# INA333_ADS1118_yusnows.net
KiCad netlist of a schematic drawn in Altium Designer
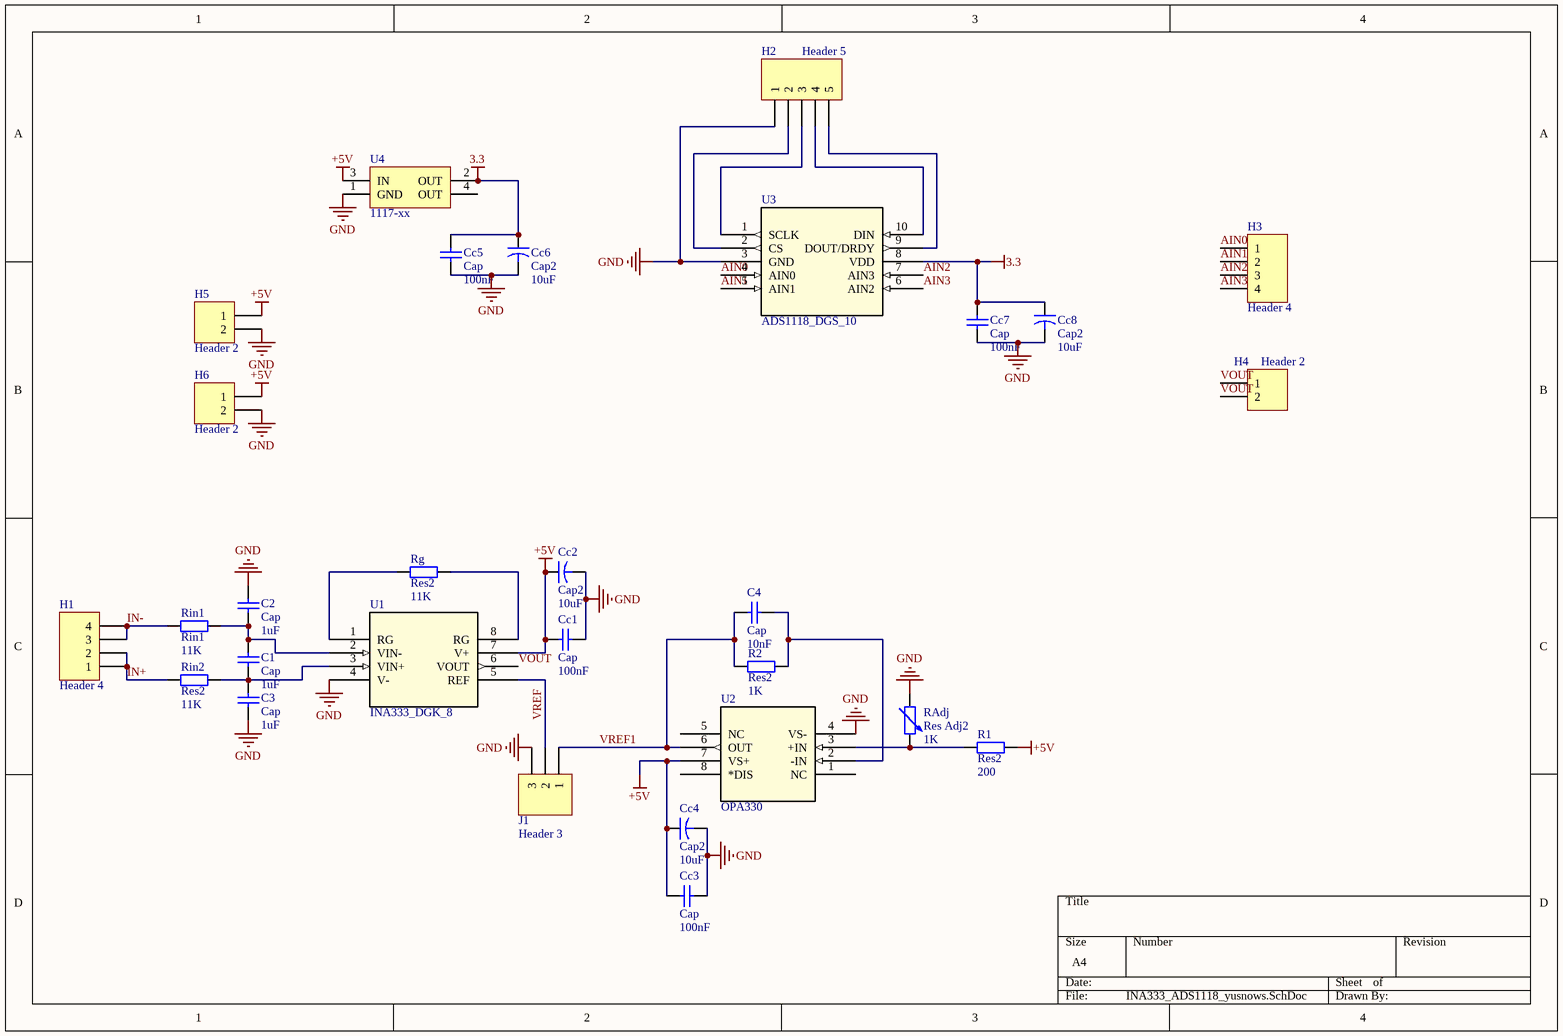
[diagram p0: INA333_ADS1118_yusnows.SchDoc]

(export (version "E")
  (design (tool "Eeschema 10.0.6"))
  (components
    (comp (ref "C1")
      (value "Cap")
      (footprint "0805C")
      (description "Capacitor")
      (fields (field (name "ALTIUM_VALUE") "1uF") (field (name "PUBLISHER") "Altium Limited"))
      (libsource (lib "Miscellaneous Devices") (part "Cap"))
    )
    (comp (ref "C2")
      (value "Cap")
      (footprint "0805C")
      (description "Capacitor")
      (fields (field (name "ALTIUM_VALUE") "1uF") (field (name "PUBLISHER") "Altium Limited"))
      (libsource (lib "Miscellaneous Devices") (part "Cap"))
    )
    (comp (ref "C3")
      (value "Cap")
      (footprint "0805C")
      (description "Capacitor")
      (fields (field (name "ALTIUM_VALUE") "1uF") (field (name "PUBLISHER") "Altium Limited"))
      (libsource (lib "Miscellaneous Devices") (part "Cap"))
    )
    (comp (ref "C4")
      (value "Cap")
      (footprint "0805C")
      (description "Capacitor")
      (fields (field (name "ALTIUM_VALUE") "10nF") (field (name "PUBLISHER") "Altium Limited"))
      (libsource (lib "Miscellaneous Devices") (part "Cap"))
    )
    (comp (ref "Cc1")
      (value "Cap")
      (footprint "0805C")
      (description "Capacitor")
      (fields (field (name "ALTIUM_VALUE") "100nF") (field (name "PUBLISHER") "Altium Limited"))
      (libsource (lib "Miscellaneous Devices") (part "Cap"))
    )
    (comp (ref "Cc2")
      (value "Cap2")
      (footprint "CAP_SMD_3216")
      (description "Capacitor")
      (fields (field (name "ALTIUM_VALUE") "10uF") (field (name "PUBLISHER") "Altium Limited"))
      (libsource (lib "Miscellaneous Devices") (part "Cap2"))
    )
    (comp (ref "Cc3")
      (value "Cap")
      (footprint "0805C")
      (description "Capacitor")
      (fields (field (name "ALTIUM_VALUE") "100nF") (field (name "PUBLISHER") "Altium Limited"))
      (libsource (lib "Miscellaneous Devices") (part "Cap"))
    )
    (comp (ref "Cc4")
      (value "Cap2")
      (footprint "CAP_SMD_3216")
      (description "Capacitor")
      (fields (field (name "ALTIUM_VALUE") "10uF") (field (name "PUBLISHER") "Altium Limited"))
      (libsource (lib "Miscellaneous Devices") (part "Cap2"))
    )
    (comp (ref "Cc5")
      (value "Cap")
      (footprint "0805C")
      (description "Capacitor")
      (fields (field (name "ALTIUM_VALUE") "100nF") (field (name "PUBLISHER") "Altium Limited"))
      (libsource (lib "Miscellaneous Devices") (part "Cap"))
    )
    (comp (ref "Cc6")
      (value "Cap2")
      (footprint "CAP_SMD_3216")
      (description "Capacitor")
      (fields (field (name "ALTIUM_VALUE") "10uF") (field (name "PUBLISHER") "Altium Limited"))
      (libsource (lib "Miscellaneous Devices") (part "Cap2"))
    )
    (comp (ref "Cc7")
      (value "Cap")
      (footprint "0805C")
      (description "Capacitor")
      (fields (field (name "ALTIUM_VALUE") "100nF") (field (name "PUBLISHER") "Altium Limited"))
      (libsource (lib "Miscellaneous Devices") (part "Cap"))
    )
    (comp (ref "Cc8")
      (value "Cap2")
      (footprint "CAP_SMD_3216")
      (description "Capacitor")
      (fields (field (name "ALTIUM_VALUE") "10uF") (field (name "PUBLISHER") "Altium Limited"))
      (libsource (lib "Miscellaneous Devices") (part "Cap2"))
    )
    (comp (ref "H1")
      (value "Header 4")
      (footprint "HDR1X4")
      (description "Header, 4-Pin")
      (fields (field (name "PUBLISHER") "Altium Limited"))
      (libsource (lib "Miscellaneous Connectors") (part "Header 4"))
    )
    (comp (ref "H2")
      (value "Header 5")
      (footprint "HDR1X5")
      (description "Header, 5-Pin")
      (fields (field (name "PUBLISHER") "Altium Limited"))
      (libsource (lib "Miscellaneous Connectors") (part "Header 5"))
    )
    (comp (ref "H3")
      (value "Header 4")
      (footprint "HDR1X4")
      (description "Header, 4-Pin")
      (fields (field (name "PUBLISHER") "Altium Limited"))
      (libsource (lib "") (part "Header 4_1"))
    )
    (comp (ref "H4")
      (value "Header 2")
      (footprint "HDR1X2")
      (description "Header, 2-Pin")
      (fields (field (name "PUBLISHER") "Altium Limited"))
      (libsource (lib "") (part "Header 2_1"))
    )
    (comp (ref "H5")
      (value "Header 2")
      (footprint "HDR1X2")
      (description "Header, 2-Pin")
      (fields (field (name "PUBLISHER") "Altium Limited"))
      (libsource (lib "Miscellaneous Connectors") (part "Header 2"))
    )
    (comp (ref "H6")
      (value "Header 2")
      (footprint "HDR1X2")
      (description "Header, 2-Pin")
      (fields (field (name "PUBLISHER") "Altium Limited"))
      (libsource (lib "Miscellaneous Connectors") (part "Header 2"))
    )
    (comp (ref "J1")
      (value "Header 3")
      (footprint "HDR1X3")
      (description "Header, 3-Pin")
      (fields (field (name "PUBLISHER") "Altium Limited"))
      (libsource (lib "Miscellaneous Connectors") (part "Header 3"))
    )
    (comp (ref "R1")
      (value "Res2")
      (footprint "0805R")
      (description "Resistor")
      (fields (field (name "ALTIUM_VALUE") "200") (field (name "PUBLISHER") "Altium Limited"))
      (libsource (lib "Miscellaneous Devices") (part "Res2"))
    )
    (comp (ref "R2")
      (value "Res2")
      (footprint "0805R")
      (description "Resistor")
      (fields (field (name "ALTIUM_VALUE") "1K") (field (name "PUBLISHER") "Altium Limited"))
      (libsource (lib "Miscellaneous Devices") (part "Res2"))
    )
    (comp (ref "RAdj")
      (value "Res Adj2")
      (footprint "PRS_POT")
      (description "Variable Resistor")
      (fields (field (name "ALTIUM_VALUE") "1K") (field (name "PUBLISHER") "Altium Limited"))
      (libsource (lib "Miscellaneous Devices") (part "Res Adj2"))
    )
    (comp (ref "Rg")
      (value "Res2")
      (footprint "0805R")
      (description "Resistor")
      (fields (field (name "ALTIUM_VALUE") "11K") (field (name "PUBLISHER") "Altium Limited"))
      (libsource (lib "Miscellaneous Devices") (part "Res2"))
    )
    (comp (ref "Rin1")
      (value "Rin1")
      (footprint "0805R")
      (description "Resistor")
      (fields (field (name "ALTIUM_VALUE") "11K") (field (name "PUBLISHER") "Altium Limited"))
      (libsource (lib "Miscellaneous Devices") (part "Res2"))
    )
    (comp (ref "Rin2")
      (value "Res2")
      (footprint "0805R")
      (description "Resistor")
      (fields (field (name "ALTIUM_VALUE") "11K") (field (name "PUBLISHER") "Altium Limited"))
      (libsource (lib "Miscellaneous Devices") (part "Res2"))
    )
    (comp (ref "U1")
      (value "INA333_DGK_8")
      (footprint "DGK8")
      (description "Imported")
      (fields (field (name "MANUFACTURER") "Texas Instruments") (field (name "GENERIC_PART_NUMBER") "INA333"))
      (libsource (lib "INA333DGK") (part "INA333_DGK_8"))
    )
    (comp (ref "U2")
      (value "OPA330")
      (footprint "D8")
      (description "Imported")
      (fields (field (name "MANUFACTURER") "Texas Instruments") (field (name "GENERIC_PART_NUMBER") "OPA691"))
      (libsource (lib "SOIC8") (part "OPA691_D_8"))
    )
    (comp (ref "U3")
      (value "ADS1118_DGS_10")
      (footprint "DGS10")
      (description "Imported")
      (fields
        (field (name "MANUFACTURER") "Texas Instruments")
        (field (name "GENERIC_PART_NUMBER") "ADS1118")
      )
      (libsource (lib "ADS1118") (part "ADS1118_DGS_10"))
    )
    (comp (ref "U4")
      (value "1117-xx")
      (footprint "SOT-223_")
      (description "稳压芯片")
      (libsource (lib "unsal_Devices") (part "1117-xx"))
    )
  )
  (nets
    (net (code "1") (name "+5V") (class "Default")
      (node (ref "Cc1") (pin "2") (pinfunction "2_2") (pintype "passive"))
      (node (ref "Cc2") (pin "1") (pinfunction "1_1") (pintype "passive"))
      (node (ref "Cc3") (pin "2") (pinfunction "2_2") (pintype "passive"))
      (node (ref "Cc4") (pin "1") (pinfunction "1_1") (pintype "passive"))
      (node (ref "H5") (pin "1") (pinfunction "1_1") (pintype "passive"))
      (node (ref "H6") (pin "1") (pinfunction "1_1") (pintype "passive"))
      (node (ref "R1") (pin "2") (pinfunction "2_2") (pintype "passive"))
      (node (ref "U1") (pin "7") (pinfunction "V+_7") (pintype "power_in"))
      (node (ref "U2") (pin "7") (pinfunction "VS+_7") (pintype "power_in"))
      (node (ref "U4") (pin "3") (pinfunction "IN_3") (pintype "passive"))
    )
    (net (code "2") (name "/AIN0") (class "Default")
      (node (ref "H3") (pin "1") (pinfunction "1_1") (pintype "passive"))
      (node (ref "U3") (pin "4") (pinfunction "AIN0_4") (pintype "input"))
    )
    (net (code "3") (name "/AIN1") (class "Default")
      (node (ref "H3") (pin "2") (pinfunction "2_2") (pintype "passive"))
      (node (ref "U3") (pin "5") (pinfunction "AIN1_5") (pintype "input"))
    )
    (net (code "4") (name "/AIN2") (class "Default")
      (node (ref "H3") (pin "3") (pinfunction "3_3") (pintype "passive"))
      (node (ref "U3") (pin "7") (pinfunction "AIN3_7") (pintype "input"))
    )
    (net (code "5") (name "/AIN3") (class "Default")
      (node (ref "H3") (pin "4") (pinfunction "4_4") (pintype "passive"))
      (node (ref "U3") (pin "6") (pinfunction "AIN2_6") (pintype "input"))
    )
    (net (code "6") (name "/IN+") (class "Default")
      (node (ref "H1") (pin "1") (pinfunction "1_1") (pintype "passive"))
      (node (ref "H1") (pin "2") (pinfunction "2_2") (pintype "passive"))
      (node (ref "Rin2") (pin "1") (pinfunction "1_1") (pintype "passive"))
    )
    (net (code "7") (name "/IN-") (class "Default")
      (node (ref "H1") (pin "3") (pinfunction "3_3") (pintype "passive"))
      (node (ref "H1") (pin "4") (pinfunction "4_4") (pintype "passive"))
      (node (ref "Rin1") (pin "1") (pinfunction "1_1") (pintype "passive"))
    )
    (net (code "8") (name "/VOUT") (class "Default")
      (node (ref "H4") (pin "1") (pinfunction "1_1") (pintype "passive"))
      (node (ref "H4") (pin "2") (pinfunction "2_2") (pintype "passive"))
      (node (ref "U1") (pin "6") (pinfunction "VOUT_6") (pintype "output"))
    )
    (net (code "9") (name "/VREF") (class "Default")
      (node (ref "J1") (pin "2") (pinfunction "2_2") (pintype "passive"))
      (node (ref "U1") (pin "5") (pinfunction "REF_5") (pintype "passive"))
    )
    (net (code "10") (name "/VREF1") (class "Default")
      (node (ref "C4") (pin "2") (pinfunction "2_2") (pintype "passive"))
      (node (ref "J1") (pin "1") (pinfunction "1_1") (pintype "passive"))
      (node (ref "R2") (pin "1") (pinfunction "1_1") (pintype "passive"))
      (node (ref "U2") (pin "6") (pinfunction "OUT_6") (pintype "output"))
    )
    (net (code "11") (name "3.3") (class "Default")
      (node (ref "Cc5") (pin "2") (pinfunction "2_2") (pintype "passive"))
      (node (ref "Cc6") (pin "1") (pinfunction "1_1") (pintype "passive"))
      (node (ref "Cc7") (pin "2") (pinfunction "2_2") (pintype "passive"))
      (node (ref "Cc8") (pin "1") (pinfunction "1_1") (pintype "passive"))
      (node (ref "U3") (pin "8") (pinfunction "VDD_8") (pintype "power_in"))
      (node (ref "U4") (pin "2") (pinfunction "OUT_2") (pintype "passive"))
    )
    (net (code "12") (name "GND") (class "Default")
      (node (ref "C2") (pin "2") (pinfunction "2_2") (pintype "passive"))
      (node (ref "C3") (pin "1") (pinfunction "1_1") (pintype "passive"))
      (node (ref "Cc1") (pin "1") (pinfunction "1_1") (pintype "passive"))
      (node (ref "Cc2") (pin "2") (pinfunction "2_2") (pintype "passive"))
      (node (ref "Cc3") (pin "1") (pinfunction "1_1") (pintype "passive"))
      (node (ref "Cc4") (pin "2") (pinfunction "2_2") (pintype "passive"))
      (node (ref "Cc5") (pin "1") (pinfunction "1_1") (pintype "passive"))
      (node (ref "Cc6") (pin "2") (pinfunction "2_2") (pintype "passive"))
      (node (ref "Cc7") (pin "1") (pinfunction "1_1") (pintype "passive"))
      (node (ref "Cc8") (pin "2") (pinfunction "2_2") (pintype "passive"))
      (node (ref "H2") (pin "1") (pinfunction "1_1") (pintype "passive"))
      (node (ref "H5") (pin "2") (pinfunction "2_2") (pintype "passive"))
      (node (ref "H6") (pin "2") (pinfunction "2_2") (pintype "passive"))
      (node (ref "J1") (pin "3") (pinfunction "3_3") (pintype "passive"))
      (node (ref "RAdj") (pin "1") (pinfunction "1_1") (pintype "passive"))
      (node (ref "U1") (pin "4") (pinfunction "V-_4") (pintype "power_in"))
      (node (ref "U2") (pin "4") (pinfunction "VS-_4") (pintype "power_in"))
      (node (ref "U3") (pin "3") (pinfunction "GND_3") (pintype "power_in"))
      (node (ref "U4") (pin "1") (pinfunction "GND_1") (pintype "passive"))
    )
    (net (code "13") (name "Net-(Rg-Pad1)") (class "Default")
      (node (ref "Rg") (pin "1") (pinfunction "1_1") (pintype "passive"))
      (node (ref "U1") (pin "1") (pinfunction "RG_1") (pintype "passive"))
    )
    (net (code "14") (name "Net-(Rg-Pad2)") (class "Default")
      (node (ref "Rg") (pin "2") (pinfunction "2_2") (pintype "passive"))
      (node (ref "U1") (pin "8") (pinfunction "RG_8") (pintype "passive"))
    )
    (net (code "15") (name "Net-(U1-VIN+)") (class "Default")
      (node (ref "C1") (pin "1") (pinfunction "1_1") (pintype "passive"))
      (node (ref "C3") (pin "2") (pinfunction "2_2") (pintype "passive"))
      (node (ref "Rin2") (pin "2") (pinfunction "2_2") (pintype "passive"))
      (node (ref "U1") (pin "3") (pinfunction "VIN+_3") (pintype "input"))
    )
    (net (code "16") (name "Net-(U1-VIN-)") (class "Default")
      (node (ref "C1") (pin "2") (pinfunction "2_2") (pintype "passive"))
      (node (ref "C2") (pin "1") (pinfunction "1_1") (pintype "passive"))
      (node (ref "Rin1") (pin "2") (pinfunction "2_2") (pintype "passive"))
      (node (ref "U1") (pin "2") (pinfunction "VIN-_2") (pintype "input"))
    )
    (net (code "17") (name "Net-(U2-+IN)") (class "Default")
      (node (ref "R1") (pin "1") (pinfunction "1_1") (pintype "passive"))
      (node (ref "RAdj") (pin "2") (pinfunction "2_2") (pintype "passive"))
      (node (ref "U2") (pin "3") (pinfunction "+IN_3") (pintype "input"))
    )
    (net (code "18") (name "Net-(U2--IN)") (class "Default")
      (node (ref "C4") (pin "1") (pinfunction "1_1") (pintype "passive"))
      (node (ref "R2") (pin "2") (pinfunction "2_2") (pintype "passive"))
      (node (ref "U2") (pin "2") (pinfunction "-IN_2") (pintype "input"))
    )
    (net (code "19") (name "Net-(U3-CS)") (class "Default")
      (node (ref "H2") (pin "2") (pinfunction "2_2") (pintype "passive"))
      (node (ref "U3") (pin "2") (pinfunction "CS_2") (pintype "output"))
    )
    (net (code "20") (name "Net-(U3-DIN)") (class "Default")
      (node (ref "H2") (pin "4") (pinfunction "4_4") (pintype "passive"))
      (node (ref "U3") (pin "10") (pinfunction "DIN_10") (pintype "input"))
    )
    (net (code "21") (name "Net-(U3-DOUT{slash}DRDY)") (class "Default")
      (node (ref "H2") (pin "5") (pinfunction "5_5") (pintype "passive"))
      (node (ref "U3") (pin "9") (pinfunction "DOUT/DRDY_9") (pintype "output"))
    )
    (net (code "22") (name "Net-(U3-SCLK)") (class "Default")
      (node (ref "H2") (pin "3") (pinfunction "3_3") (pintype "passive"))
      (node (ref "U3") (pin "1") (pinfunction "SCLK_1") (pintype "output"))
    )
    (net (code "23") (name "unconnected-(U2-*DIS-Pad8)") (class "Default")
      (node (ref "U2") (pin "8") (pinfunction "*DIS_8") (pintype "passive"))
    )
    (net (code "24") (name "unconnected-(U2-NC-Pad1)") (class "Default")
      (node (ref "U2") (pin "1") (pinfunction "NC_1") (pintype "passive"))
    )
    (net (code "25") (name "unconnected-(U2-NC-Pad5)") (class "Default")
      (node (ref "U2") (pin "5") (pinfunction "NC_5") (pintype "passive"))
    )
    (net (code "26") (name "unconnected-(U4-OUT-Pad4)") (class "Default")
      (node (ref "U4") (pin "4") (pinfunction "OUT_4") (pintype "passive"))
    )
  )
)
